# fiber.net
KiCad netlist of a schematic drawn in Altium Designer
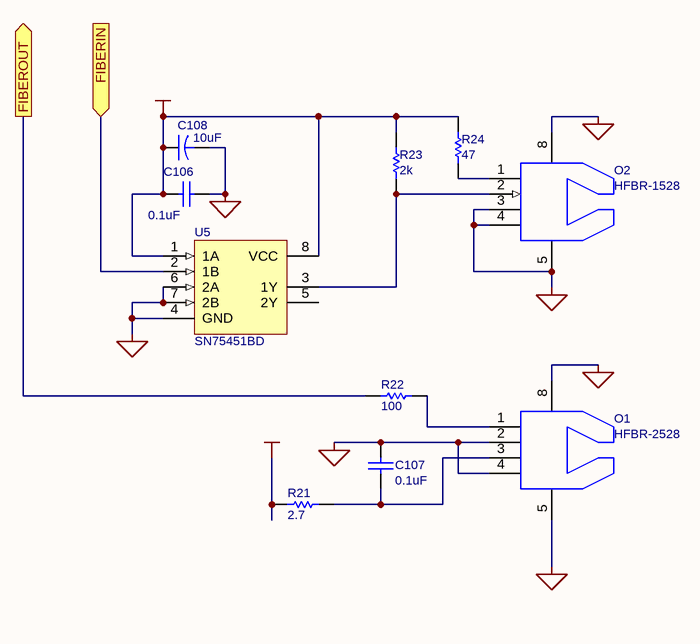
[diagram p0: fiber.SCHDOC]

(export (version "E")
  (design (tool "Eeschema 10.0.6"))
  (components
    (comp (ref "C106")
      (value "0.1uF")
      (footprint "CC1005-0402")
      (description "Capacitor")
      (fields
        (field (name "MANUFACTURER") "Generic Components")
        (field (name "Comment") "Cap")
        (field (name "PUBLISHER") "Altium Limited")
      )
      (libsource (lib "Miscellaneous Devices") (part "Cap"))
    )
    (comp (ref "C107")
      (value "0.1uF")
      (footprint "CC1005-0402")
      (description "Capacitor")
      (fields
        (field (name "MANUFACTURER") "Generic Components")
        (field (name "Comment") "Cap")
        (field (name "PUBLISHER") "Altium Limited")
      )
      (libsource (lib "Miscellaneous Devices") (part "Cap"))
    )
    (comp (ref "C108")
      (value "10uF")
      (footprint "TC3528-1411")
      (description "Capacitor")
      (fields (field (name "MANUFACTURER") "Generic Components") (field (name "PUBLISHER") "Altium Limited"))
      (libsource (lib "Miscellaneous Devices") (part "Cap2"))
    )
    (comp (ref "O1")
      (value "HFBR-2528")
      (footprint "HPVL")
      (description "Low-cost fiber receiver")
      (libsource (lib "parts") (part "HFBR-2528"))
    )
    (comp (ref "O2")
      (value "HFBR-1528")
      (footprint "HPVL")
      (description "Low-cost fiber transmitter")
      (libsource (lib "parts") (part "HFBR-1528"))
    )
    (comp (ref "R21")
      (value "2.7")
      (footprint "CR1608-0603")
      (description "Resistor")
      (fields
        (field (name "MANUFACTURER") "Generic Components")
        (field (name "Comment") "Res1")
        (field (name "PUBLISHER") "Altium Limited")
      )
      (libsource (lib "Miscellaneous Devices") (part "Res1"))
    )
    (comp (ref "R22")
      (value "100")
      (footprint "CR1608-0603")
      (description "Resistor")
      (fields
        (field (name "MANUFACTURER") "Generic Components")
        (field (name "Comment") "Res1")
        (field (name "PUBLISHER") "Altium Limited")
      )
      (libsource (lib "Miscellaneous Devices") (part "Res1"))
    )
    (comp (ref "R23")
      (value "2k")
      (footprint "CR1608-0603")
      (description "Resistor")
      (fields
        (field (name "MANUFACTURER") "Generic Components")
        (field (name "Comment") "Res1")
        (field (name "PUBLISHER") "Altium Limited")
      )
      (libsource (lib "Miscellaneous Devices") (part "Res1"))
    )
    (comp (ref "R24")
      (value "47")
      (footprint "CR1608-0603")
      (description "Resistor")
      (fields
        (field (name "MANUFACTURER") "Generic Components")
        (field (name "Comment") "Res1")
        (field (name "PUBLISHER") "Altium Limited")
      )
      (libsource (lib "Miscellaneous Devices") (part "Res1"))
    )
    (comp (ref "U5")
      (value "SN75451BD")
      (footprint "SO-G8/E2.5")
      (description "Dual Peripheral Driver")
      (fields (field (name "MANUFACTURER") "Texas Instruments") (field (name "PUBLISHER") "Altium Limited"))
      (libsource (lib "TI Interface Peripheral Driver") (part "SN75451BD"))
    )
  )
  (nets
    (net (code "1") (name "+5VCC") (class "Default")
      (node (ref "C106") (pin "1") (pinfunction "1_1") (pintype "passive"))
      (node (ref "C108") (pin "1") (pinfunction "1_1") (pintype "passive"))
      (node (ref "R21") (pin "1") (pinfunction "1_1") (pintype "passive"))
      (node (ref "R23") (pin "2") (pinfunction "2_2") (pintype "passive"))
      (node (ref "R24") (pin "2") (pinfunction "2_2") (pintype "passive"))
      (node (ref "U5") (pin "1") (pinfunction "1A_1") (pintype "input"))
      (node (ref "U5") (pin "8") (pinfunction "VCC_8") (pintype "power_in"))
    )
    (net (code "2") (name "/FIBERIN") (class "Default")
      (node (ref "U5") (pin "2") (pinfunction "1B_2") (pintype "input"))
    )
    (net (code "3") (name "/FIBEROUT") (class "Default")
      (node (ref "R22") (pin "1") (pinfunction "1_1") (pintype "passive"))
    )
    (net (code "4") (name "GND") (class "Default")
      (node (ref "C106") (pin "2") (pinfunction "2_2") (pintype "passive"))
      (node (ref "C107") (pin "2") (pinfunction "2_2") (pintype "passive"))
      (node (ref "C108") (pin "2") (pinfunction "2_2") (pintype "passive"))
      (node (ref "O1") (pin "2") (pintype "power_in"))
      (node (ref "O1") (pin "4") (pintype "power_in"))
      (node (ref "O1") (pin "5") (pintype "power_in"))
      (node (ref "O1") (pin "8") (pintype "power_in"))
      (node (ref "O2") (pin "3") (pintype "power_in"))
      (node (ref "O2") (pin "4") (pintype "power_in"))
      (node (ref "O2") (pin "5") (pintype "power_in"))
      (node (ref "O2") (pin "8") (pintype "power_in"))
      (node (ref "U5") (pin "4") (pinfunction "GND_4") (pintype "power_in"))
      (node (ref "U5") (pin "6") (pinfunction "2A_6") (pintype "input"))
      (node (ref "U5") (pin "7") (pinfunction "2B_7") (pintype "input"))
    )
    (net (code "5") (name "Net-(C107-Pad1)") (class "Default")
      (node (ref "C107") (pin "1") (pinfunction "1_1") (pintype "passive"))
      (node (ref "O1") (pin "3") (pintype "power_in"))
      (node (ref "R21") (pin "2") (pinfunction "2_2") (pintype "passive"))
    )
    (net (code "6") (name "Net-(O1-Pad1)") (class "Default")
      (node (ref "O1") (pin "1") (pintype "power_in"))
      (node (ref "R22") (pin "2") (pinfunction "2_2") (pintype "passive"))
    )
    (net (code "7") (name "Net-(O2-Pad1)") (class "Default")
      (node (ref "O2") (pin "1") (pintype "power_in"))
      (node (ref "R24") (pin "1") (pinfunction "1_1") (pintype "passive"))
    )
    (net (code "8") (name "Net-(U5-1Y)") (class "Default")
      (node (ref "O2") (pin "2") (pintype "input"))
      (node (ref "R23") (pin "1") (pinfunction "1_1") (pintype "passive"))
      (node (ref "U5") (pin "3") (pinfunction "1Y_3") (pintype "open_collector"))
    )
    (net (code "9") (name "unconnected-(U5-2Y-Pad5)") (class "Default")
      (node (ref "U5") (pin "5") (pinfunction "2Y_5") (pintype "open_collector"))
    )
  )
)
